# Bee_Hive_MainBoard.net
KiCad netlist of a schematic drawn in Altium Designer
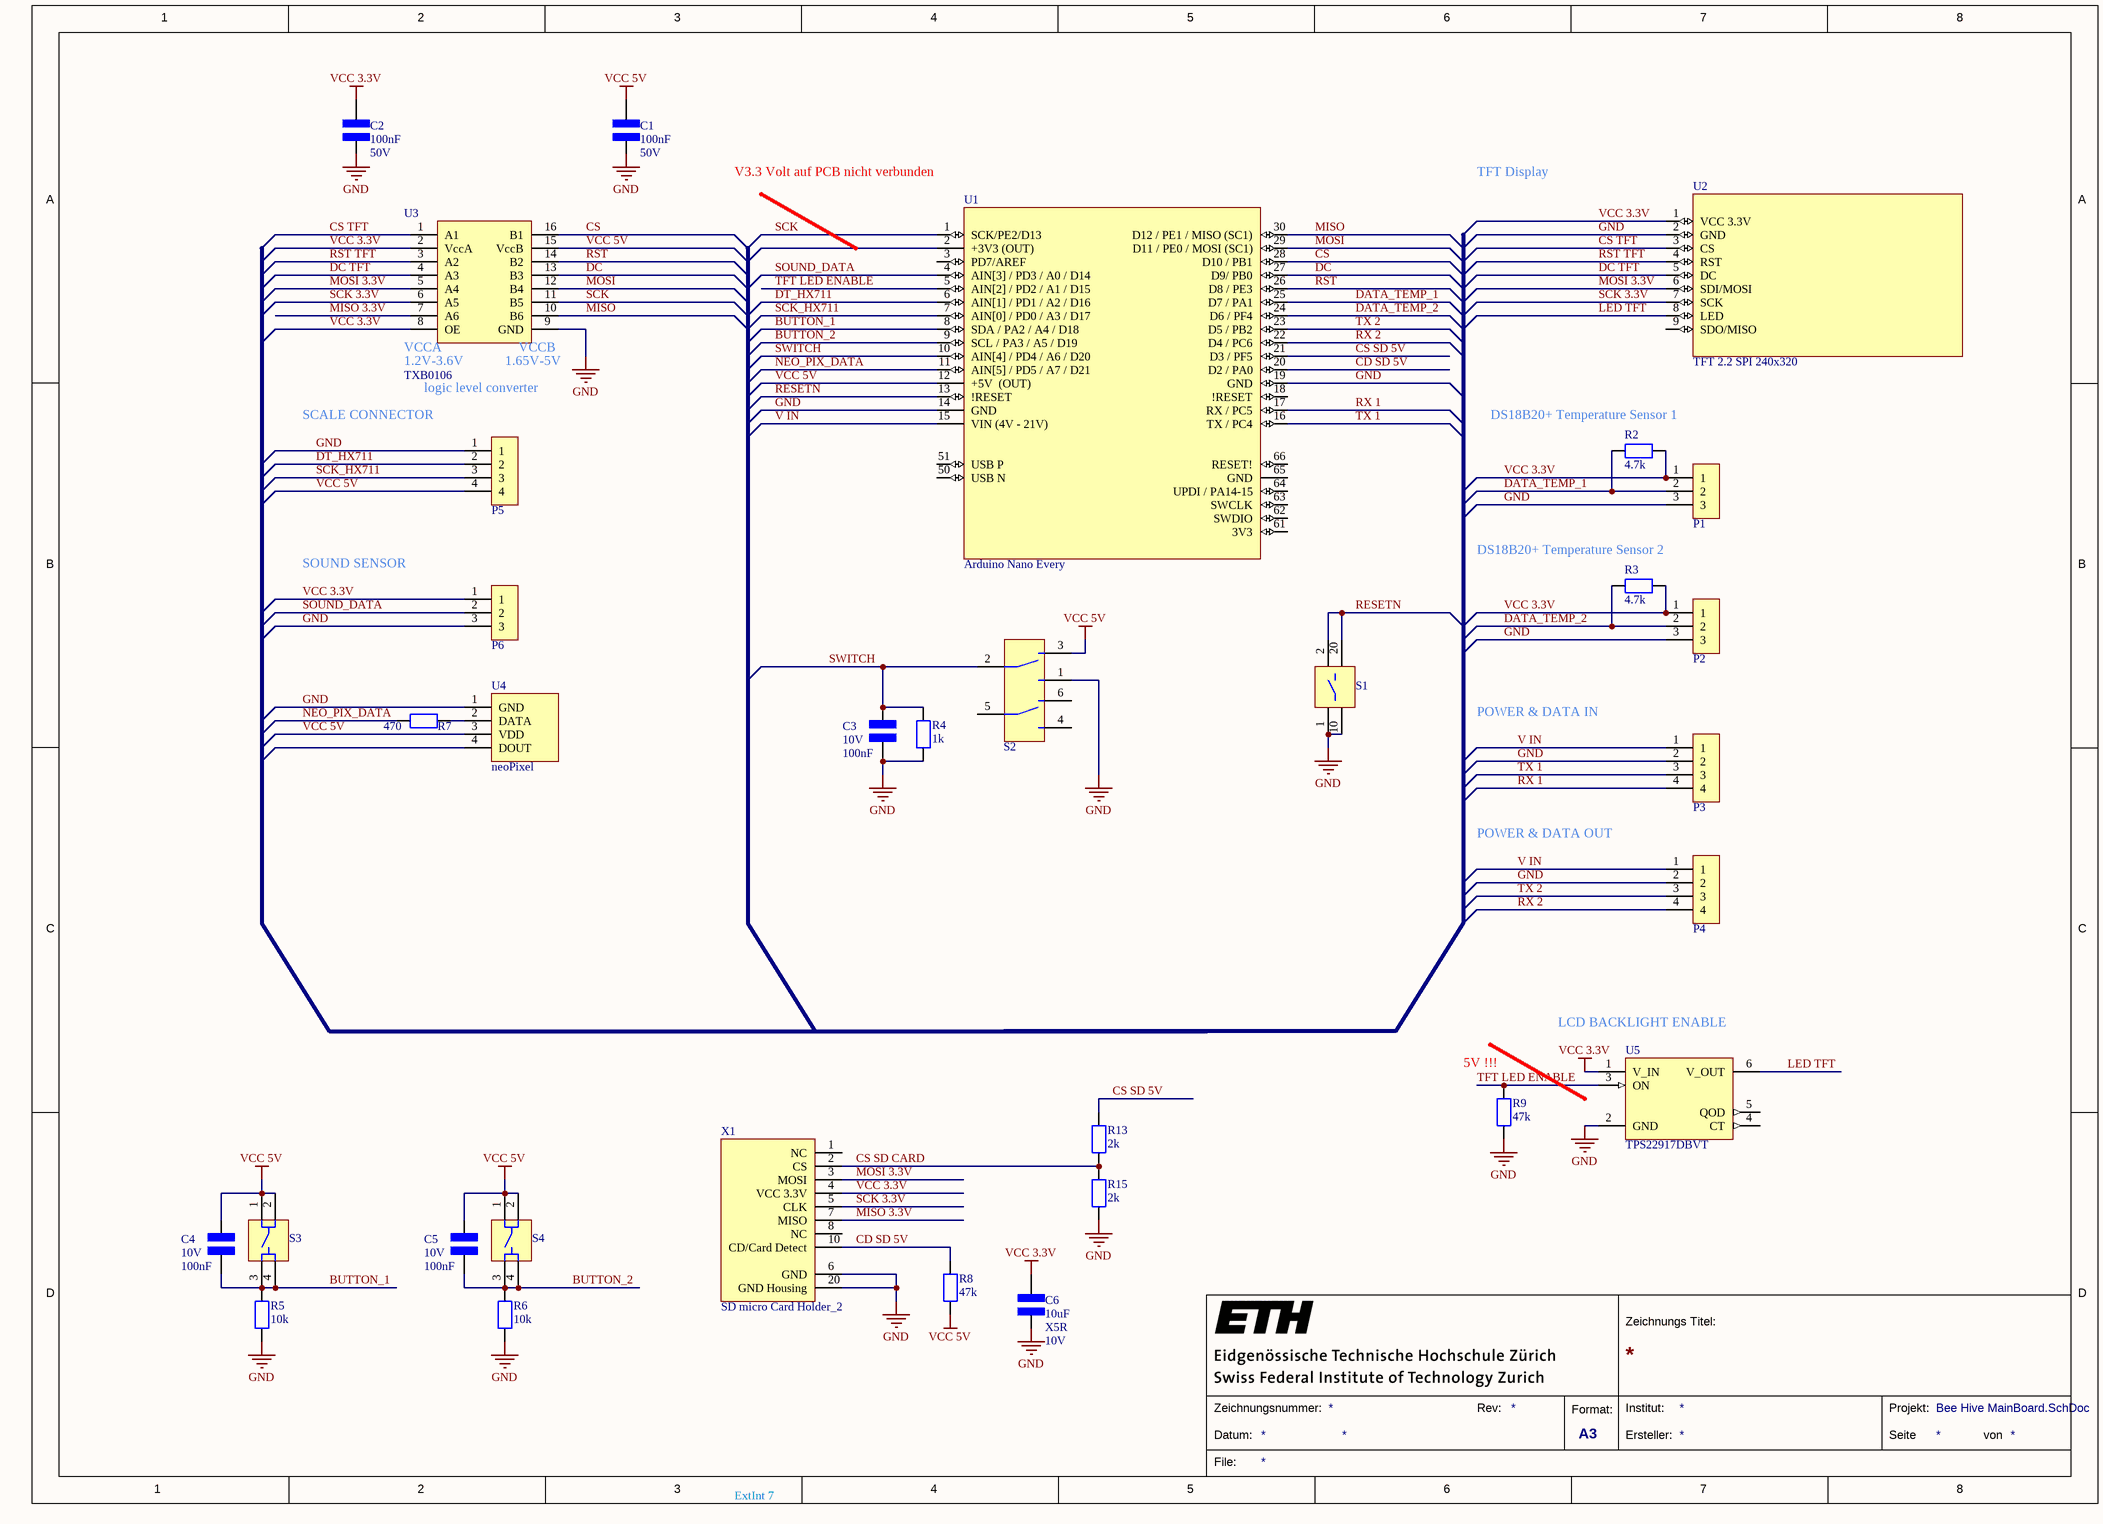
[diagram p0: Bee Hive MainBoard.SchDoc]

(export (version "E")
  (design (tool "Eeschema 10.0.6"))
  (components
    (comp (ref "C1")
      (value "100nF")
      (footprint "CAP 0603")
      (description "C CERAMIC SMD")
      (fields (field (name "UMAX") "50V") (field (name "Comment") "100nF 0603_1"))
      (libsource (lib "Library CAP") (part "100nF 0603_1"))
    )
    (comp (ref "C2")
      (value "100nF")
      (footprint "CAP 0603")
      (description "C CERAMIC SMD")
      (fields (field (name "UMAX") "50V") (field (name "Comment") "100nF 0603_1"))
      (libsource (lib "Library CAP") (part "100nF 0603_1"))
    )
    (comp (ref "C3")
      (value "100nF")
      (footprint "CAP 0603")
      (description "C CERAMIC SMD")
      (fields (field (name "UMAX") "10V") (field (name "Comment") "100nF 0603"))
      (libsource (lib "Library CAP") (part "100nF 0603"))
    )
    (comp (ref "C4")
      (value "100nF")
      (footprint "CAP 0603")
      (description "C CERAMIC SMD")
      (fields (field (name "UMAX") "10V") (field (name "Comment") "100nF 0603"))
      (libsource (lib "Library CAP") (part "100nF 0603"))
    )
    (comp (ref "C5")
      (value "100nF")
      (footprint "CAP 0603")
      (description "C CERAMIC SMD")
      (fields (field (name "UMAX") "10V") (field (name "Comment") "100nF 0603"))
      (libsource (lib "Library CAP") (part "100nF 0603"))
    )
    (comp (ref "C6")
      (value "10uF")
      (footprint "CAP 0603")
      (description "C CERAMIC SMD")
      (fields
        (field (name "DIELEKTRIKUM") "X5R")
        (field (name "UMAX") "10V")
        (field (name "Comment") "10uF 0603")
      )
      (libsource (lib "Library CAP") (part "10uF 0603"))
    )
    (comp (ref "P1")
      (value "3-Pin Right Angle Housing")
      (footprint "3PIN - RND 205-EK254-2.54-03P")
      (description "3-Pin")
      (libsource (lib "Library Scematic") (part "3-Pin Screw Terminal"))
    )
    (comp (ref "P2")
      (value "3-Pin Right Angle Housing")
      (footprint "3PIN - RND 205-EK254-2.54-03P")
      (description "3-Pin")
      (libsource (lib "Library Scematic") (part "3-Pin Screw Terminal"))
    )
    (comp (ref "P3")
      (value "4-Pin Right Angle Housing")
      (footprint "4PIN - RND 205-EK254-2.54-04P")
      (description "4-Pin")
      (libsource (lib "Library Scematic") (part "4-Pin Screw Terminal"))
    )
    (comp (ref "P4")
      (value "4-Pin Right Angle Housing")
      (footprint "4PIN - RND 205-EK254-2.54-04P")
      (description "4-Pin")
      (libsource (lib "Library Scematic") (part "4-Pin Screw Terminal"))
    )
    (comp (ref "P5")
      (value "4-Pin Right Angle Housing")
      (footprint "4PIN - RND 205-EK254-2.54-04P")
      (description "4-Pin")
      (libsource (lib "Library Scematic") (part "4-Pin Screw Terminal"))
    )
    (comp (ref "P6")
      (value "3-Pin Right Angle Housing")
      (footprint "3PIN - RND 205-EK254-2.54-03P")
      (description "3-Pin")
      (libsource (lib "Library Scematic") (part "3-Pin Screw Terminal"))
    )
    (comp (ref "R2")
      (value "4.7k")
      (footprint "RES 0603 FOOTPRINT")
      (description "R SMD")
      (fields (field (name "Comment") "4.7k Ohm 0603"))
      (libsource (lib "Library RES") (part "4.7k Ohm 0603"))
    )
    (comp (ref "R3")
      (value "4.7k")
      (footprint "RES 0603 FOOTPRINT")
      (description "R SMD")
      (fields (field (name "Comment") "4.7k Ohm 0603"))
      (libsource (lib "Library RES") (part "4.7k Ohm 0603"))
    )
    (comp (ref "R4")
      (value "1k")
      (footprint "RES 0603 FOOTPRINT")
      (description "R SMD")
      (fields (field (name "Comment") "1k Ohm 0603"))
      (libsource (lib "Library RES") (part "1k Ohm 0603"))
    )
    (comp (ref "R5")
      (value "10k")
      (footprint "RES 0603 FOOTPRINT")
      (description "R SMD")
      (fields (field (name "Comment") "10k Ohm 0603"))
      (libsource (lib "Library RES") (part "10k Ohm 0603"))
    )
    (comp (ref "R6")
      (value "10k")
      (footprint "RES 0603 FOOTPRINT")
      (description "R SMD")
      (fields (field (name "Comment") "10k Ohm 0603"))
      (libsource (lib "Library RES") (part "10k Ohm 0603"))
    )
    (comp (ref "R7")
      (value "470")
      (footprint "RES 0603 FOOTPRINT")
      (description "R SMD")
      (fields (field (name "Comment") "470 Ohm 0603"))
      (libsource (lib "Library RES") (part "470 Ohm 0603"))
    )
    (comp (ref "R8")
      (value "47k")
      (footprint "RES 0603 FOOTPRINT")
      (description "R SMD")
      (fields (field (name "Comment") "47k Ohm 0603"))
      (libsource (lib "Library RES") (part "47k Ohm 0603"))
    )
    (comp (ref "R9")
      (value "47k")
      (footprint "RES 0402 FOOTPRINT")
      (description "R SMD")
      (fields (field (name "Comment") "47k Ohm 0402"))
      (libsource (lib "Library RES") (part "47k Ohm 0402"))
    )
    (comp (ref "R13")
      (value "2k")
      (footprint "RES 0603 FOOTPRINT")
      (description "R SMD")
      (fields (field (name "Comment") "2k Ohm 0603"))
      (libsource (lib "Library RES") (part "2k Ohm 0603"))
    )
    (comp (ref "R15")
      (value "2k")
      (footprint "RES 0603 FOOTPRINT")
      (description "R SMD")
      (fields (field (name "Comment") "2k Ohm 0603"))
      (libsource (lib "Library RES") (part "2k Ohm 0603"))
    )
    (comp (ref "S1")
      (value "Taster Print_SMD_2")
      (footprint "Taster Print - SMD - KMR241G LFS")
      (description "Taster")
      (libsource (lib "Library Scematic") (part "Taster Print_SMD_2"))
    )
    (comp (ref "S2")
      (value "Schiebeschalter EG2207")
      (footprint "Schiebeschalter on-on 2 P, EG2207")
      (description "Schiebeschalter on-on PCM12SMTR")
      (libsource (lib "Library Scematic") (part "Schiebeschalter EG2207"))
    )
    (comp (ref "S3")
      (value "Taster Print_SMD_3")
      (footprint "Taster Print - SMD - PTS647SM70SMTR2LFS")
      (description "Taster")
      (libsource (lib "Library Scematic") (part "Taster Print_SMD_6"))
    )
    (comp (ref "S4")
      (value "Taster Print_SMD_3")
      (footprint "Taster Print - SMD - PTS647SM70SMTR2LFS")
      (description "Taster")
      (libsource (lib "Library Scematic") (part "Taster Print_SMD_6"))
    )
    (comp (ref "U1")
      (value "Arduino Nano Every")
      (footprint "Arduino Nano Every")
      (description "https://store.arduino.cc/nano-every-pack")
      (libsource (lib "Library Scematic") (part "Arduino Nano Every"))
    )
    (comp (ref "U2")
      (value "TFT 2.2 SPI 240x320")
      (footprint "TFT 2.2 SPI 240x320")
      (libsource (lib "Library Scematic") (part "TFT 2.2 SPI 240x320"))
    )
    (comp (ref "U3")
      (value "TXB0106")
      (footprint "TSSOP-16L")
      (description "Level Converter TXB0106")
      (libsource (lib "Library Scematic") (part "TXB0106 Level Converter"))
    )
    (comp (ref "U4")
      (value "neoPixel")
      (footprint "neoPixel 5050 adafruit 1655")
      (description "neoPixel 5050 adafruit 1655")
      (libsource (lib "Library Scematic") (part "neoPixel 5050 adafruit 1655"))
    )
    (comp (ref "U5")
      (value "TPS22917DBVT")
      (footprint "SOT23 - 6")
      (description "High Side Switch")
      (libsource (lib "Library Scematic") (part "TPS22917DBVT"))
    )
    (comp (ref "X1")
      (value "SD micro Card Holder_2")
      (footprint "SD Card Holder - micro - 2 - sd Card inserted")
      (description "SD micro Card  Holder")
      (libsource (lib "Library Scematic") (part "SD micro Card Holder_2"))
    )
  )
  (nets
    (net (code "1") (name "/BUTTON_1") (class "Default")
      (node (ref "C4") (pin "2") (pinfunction "2_2") (pintype "passive"))
      (node (ref "R5") (pin "2") (pinfunction "2_2") (pintype "passive"))
      (node (ref "S3") (pin "3") (pinfunction "3_3") (pintype "passive"))
      (node (ref "S3") (pin "4") (pinfunction "4_4") (pintype "passive"))
      (node (ref "U1") (pin "8") (pinfunction "SDA_/_PA2_/_A4_/_D18_8") (pintype "bidirectional"))
    )
    (net (code "2") (name "/BUTTON_2") (class "Default")
      (node (ref "C5") (pin "2") (pinfunction "2_2") (pintype "passive"))
      (node (ref "R6") (pin "2") (pinfunction "2_2") (pintype "passive"))
      (node (ref "S4") (pin "3") (pinfunction "3_3") (pintype "passive"))
      (node (ref "S4") (pin "4") (pinfunction "4_4") (pintype "passive"))
      (node (ref "U1") (pin "9") (pinfunction "SCL_/_PA3_/_A5_/_D19_9") (pintype "bidirectional"))
    )
    (net (code "3") (name "/CD SD 5V") (class "Default")
      (node (ref "R8") (pin "1") (pinfunction "1_1") (pintype "passive"))
      (node (ref "U1") (pin "20") (pinfunction "D2_/_PA0_20") (pintype "bidirectional"))
      (node (ref "X1") (pin "10") (pinfunction "CD/Card_Detect_10") (pintype "passive"))
    )
    (net (code "4") (name "/CS") (class "Default")
      (node (ref "U1") (pin "28") (pinfunction "D10_/_PB1_28") (pintype "bidirectional"))
      (node (ref "U3") (pin "16") (pinfunction "B1_16") (pintype "passive"))
    )
    (net (code "5") (name "/CS SD 5V") (class "Default")
      (node (ref "R13") (pin "2") (pinfunction "2_2") (pintype "passive"))
      (node (ref "U1") (pin "21") (pinfunction "D3_/_PF5_21") (pintype "bidirectional"))
    )
    (net (code "6") (name "/CS SD CARD") (class "Default")
      (node (ref "R13") (pin "1") (pinfunction "1_1") (pintype "passive"))
      (node (ref "R15") (pin "2") (pinfunction "2_2") (pintype "passive"))
      (node (ref "X1") (pin "2") (pinfunction "CS_2") (pintype "passive"))
    )
    (net (code "7") (name "/CS TFT") (class "Default")
      (node (ref "U2") (pin "3") (pinfunction "CS_3") (pintype "bidirectional"))
      (node (ref "U3") (pin "1") (pinfunction "A1_1") (pintype "power_in"))
    )
    (net (code "8") (name "/DATA_TEMP_1") (class "Default")
      (node (ref "P1") (pin "2") (pinfunction "2_2") (pintype "passive"))
      (node (ref "R2") (pin "2") (pinfunction "2_2") (pintype "passive"))
      (node (ref "U1") (pin "25") (pinfunction "D7_/_PA1_25") (pintype "bidirectional"))
    )
    (net (code "9") (name "/DATA_TEMP_2") (class "Default")
      (node (ref "P2") (pin "2") (pinfunction "2_2") (pintype "passive"))
      (node (ref "R3") (pin "2") (pinfunction "2_2") (pintype "passive"))
      (node (ref "U1") (pin "24") (pinfunction "D6_/_PF4_24") (pintype "bidirectional"))
    )
    (net (code "10") (name "/DC") (class "Default")
      (node (ref "U1") (pin "27") (pinfunction "D9/_PB0_27") (pintype "bidirectional"))
      (node (ref "U3") (pin "13") (pinfunction "B3_13") (pintype "passive"))
    )
    (net (code "11") (name "/DC TFT") (class "Default")
      (node (ref "U2") (pin "5") (pinfunction "DC_5") (pintype "bidirectional"))
      (node (ref "U3") (pin "4") (pinfunction "A3_4") (pintype "passive"))
    )
    (net (code "12") (name "/DT_HX711") (class "Default")
      (node (ref "P5") (pin "2") (pinfunction "2_2") (pintype "passive"))
      (node (ref "U1") (pin "6") (pinfunction "AIN[1]_/_PD1_/_A2_/_D16_6") (pintype "bidirectional"))
    )
    (net (code "13") (name "/LED TFT") (class "Default")
      (node (ref "U2") (pin "8") (pinfunction "LED_8") (pintype "bidirectional"))
      (node (ref "U5") (pin "6") (pinfunction "V_OUT_6") (pintype "power_in"))
    )
    (net (code "14") (name "/MISO") (class "Default")
      (node (ref "U1") (pin "30") (pinfunction "D12_/_PE1_/_MISO_(SC1)_30") (pintype "bidirectional"))
      (node (ref "U3") (pin "10") (pinfunction "B6_10") (pintype "passive"))
    )
    (net (code "15") (name "/MISO 3.3V") (class "Default")
      (node (ref "U3") (pin "7") (pinfunction "A6_7") (pintype "passive"))
      (node (ref "X1") (pin "7") (pinfunction "MISO_7") (pintype "passive"))
    )
    (net (code "16") (name "/MOSI") (class "Default")
      (node (ref "U1") (pin "29") (pinfunction "D11_/_PE0_/_MOSI_(SC1)_29") (pintype "bidirectional"))
      (node (ref "U3") (pin "12") (pinfunction "B4_12") (pintype "passive"))
    )
    (net (code "17") (name "/MOSI 3.3V") (class "Default")
      (node (ref "U2") (pin "6") (pinfunction "SDI/MOSI_6") (pintype "bidirectional"))
      (node (ref "U3") (pin "5") (pinfunction "A4_5") (pintype "passive"))
      (node (ref "X1") (pin "3") (pinfunction "MOSI_3") (pintype "passive"))
    )
    (net (code "18") (name "/NEO_PIX_DATA") (class "Default")
      (node (ref "R7") (pin "1") (pinfunction "1_1") (pintype "passive"))
      (node (ref "U1") (pin "11") (pinfunction "AIN[5]_/_PD5_/_A7_/_D21_11") (pintype "bidirectional"))
    )
    (net (code "19") (name "/RESETN") (class "Default")
      (node (ref "S1") (pin "2") (pinfunction "2_2") (pintype "passive"))
      (node (ref "S1") (pin "20") (pinfunction "20_20") (pintype "passive"))
      (node (ref "U1") (pin "13") (pinfunction "!RESET_13") (pintype "bidirectional"))
    )
    (net (code "20") (name "/RST") (class "Default")
      (node (ref "U1") (pin "26") (pinfunction "D8_/_PE3_26") (pintype "bidirectional"))
      (node (ref "U3") (pin "14") (pinfunction "B2_14") (pintype "passive"))
    )
    (net (code "21") (name "/RST TFT") (class "Default")
      (node (ref "U2") (pin "4") (pinfunction "RST_4") (pintype "bidirectional"))
      (node (ref "U3") (pin "3") (pinfunction "A2_3") (pintype "passive"))
    )
    (net (code "22") (name "/RX 1") (class "Default")
      (node (ref "P3") (pin "4") (pinfunction "4_4") (pintype "passive"))
      (node (ref "U1") (pin "17") (pinfunction "RX_/_PC5_17") (pintype "bidirectional"))
    )
    (net (code "23") (name "/RX 2") (class "Default")
      (node (ref "P4") (pin "4") (pinfunction "4_4") (pintype "passive"))
      (node (ref "U1") (pin "22") (pinfunction "D4_/_PC6_22") (pintype "bidirectional"))
    )
    (net (code "24") (name "/SCK") (class "Default")
      (node (ref "U1") (pin "1") (pinfunction "SCK/PE2/D13_1") (pintype "bidirectional"))
      (node (ref "U3") (pin "11") (pinfunction "B5_11") (pintype "passive"))
    )
    (net (code "25") (name "/SCK 3.3V") (class "Default")
      (node (ref "U2") (pin "7") (pinfunction "SCK_7") (pintype "bidirectional"))
      (node (ref "U3") (pin "6") (pinfunction "A5_6") (pintype "passive"))
      (node (ref "X1") (pin "5") (pinfunction "CLK_5") (pintype "passive"))
    )
    (net (code "26") (name "/SCK_HX711") (class "Default")
      (node (ref "P5") (pin "3") (pinfunction "3_3") (pintype "passive"))
      (node (ref "U1") (pin "7") (pinfunction "AIN[0]_/_PD0_/_A3_/_D17_7") (pintype "bidirectional"))
    )
    (net (code "27") (name "/SOUND_DATA") (class "Default")
      (node (ref "P6") (pin "2") (pinfunction "2_2") (pintype "passive"))
      (node (ref "U1") (pin "4") (pinfunction "AIN[3]_/_PD3_/_A0_/_D14_4") (pintype "bidirectional"))
    )
    (net (code "28") (name "/SWITCH") (class "Default")
      (node (ref "C3") (pin "1") (pinfunction "1_1") (pintype "passive"))
      (node (ref "R4") (pin "2") (pinfunction "2_2") (pintype "passive"))
      (node (ref "S2") (pin "2") (pinfunction "2_2") (pintype "passive"))
      (node (ref "U1") (pin "10") (pinfunction "AIN[4]_/_PD4_/_A6_/_D20_10") (pintype "bidirectional"))
    )
    (net (code "29") (name "/TFT LED ENABLE") (class "Default")
      (node (ref "R9") (pin "2") (pinfunction "2_2") (pintype "passive"))
      (node (ref "U1") (pin "5") (pinfunction "AIN[2]_/_PD2_/_A1_/_D15_5") (pintype "bidirectional"))
      (node (ref "U5") (pin "3") (pinfunction "ON_3") (pintype "input"))
    )
    (net (code "30") (name "/TX 1") (class "Default")
      (node (ref "P3") (pin "3") (pinfunction "3_3") (pintype "passive"))
      (node (ref "U1") (pin "16") (pinfunction "TX_/_PC4_16") (pintype "bidirectional"))
    )
    (net (code "31") (name "/TX 2") (class "Default")
      (node (ref "P4") (pin "3") (pinfunction "3_3") (pintype "passive"))
      (node (ref "U1") (pin "23") (pinfunction "D5_/_PB2_23") (pintype "bidirectional"))
    )
    (net (code "32") (name "/V IN") (class "Default")
      (node (ref "P3") (pin "1") (pinfunction "1_1") (pintype "passive"))
      (node (ref "P4") (pin "1") (pinfunction "1_1") (pintype "passive"))
      (node (ref "U1") (pin "15") (pinfunction "VIN_(4V_-_21V)_15") (pintype "power_in"))
    )
    (net (code "33") (name "GND") (class "Default")
      (node (ref "C1") (pin "1") (pinfunction "1_1") (pintype "passive"))
      (node (ref "C2") (pin "1") (pinfunction "1_1") (pintype "passive"))
      (node (ref "C3") (pin "2") (pinfunction "2_2") (pintype "passive"))
      (node (ref "C6") (pin "1") (pinfunction "1_1") (pintype "passive"))
      (node (ref "P1") (pin "3") (pinfunction "3_3") (pintype "passive"))
      (node (ref "P2") (pin "3") (pinfunction "3_3") (pintype "passive"))
      (node (ref "P3") (pin "2") (pinfunction "2_2") (pintype "passive"))
      (node (ref "P4") (pin "2") (pinfunction "2_2") (pintype "passive"))
      (node (ref "P5") (pin "1") (pinfunction "1_1") (pintype "passive"))
      (node (ref "P6") (pin "3") (pinfunction "3_3") (pintype "passive"))
      (node (ref "R15") (pin "1") (pinfunction "1_1") (pintype "passive"))
      (node (ref "R4") (pin "1") (pinfunction "1_1") (pintype "passive"))
      (node (ref "R5") (pin "1") (pinfunction "1_1") (pintype "passive"))
      (node (ref "R6") (pin "1") (pinfunction "1_1") (pintype "passive"))
      (node (ref "R9") (pin "1") (pinfunction "1_1") (pintype "passive"))
      (node (ref "S1") (pin "1") (pinfunction "1_1") (pintype "passive"))
      (node (ref "S1") (pin "10") (pinfunction "10_10") (pintype "passive"))
      (node (ref "S2") (pin "1") (pinfunction "1_1") (pintype "passive"))
      (node (ref "U1") (pin "14") (pinfunction "GND_14") (pintype "power_in"))
      (node (ref "U1") (pin "19") (pinfunction "GND_19") (pintype "bidirectional"))
      (node (ref "U2") (pin "2") (pinfunction "GND_2") (pintype "bidirectional"))
      (node (ref "U3") (pin "9") (pinfunction "GND_9") (pintype "passive"))
      (node (ref "U4") (pin "1") (pinfunction "GND_1") (pintype "passive"))
      (node (ref "U5") (pin "2") (pinfunction "GND_2") (pintype "power_in"))
      (node (ref "X1") (pin "20") (pinfunction "GND_Housing_20") (pintype "passive"))
      (node (ref "X1") (pin "6") (pinfunction "GND_6") (pintype "passive"))
    )
    (net (code "34") (name "Net-(U4-DATA)") (class "Default")
      (node (ref "R7") (pin "2") (pinfunction "2_2") (pintype "passive"))
      (node (ref "U4") (pin "2") (pinfunction "DATA_2") (pintype "passive"))
    )
    (net (code "35") (name "VCC 3.3V") (class "Default")
      (node (ref "C2") (pin "2") (pinfunction "2_2") (pintype "passive"))
      (node (ref "C6") (pin "2") (pinfunction "2_2") (pintype "passive"))
      (node (ref "P1") (pin "1") (pinfunction "1_1") (pintype "passive"))
      (node (ref "P2") (pin "1") (pinfunction "1_1") (pintype "passive"))
      (node (ref "P6") (pin "1") (pinfunction "1_1") (pintype "passive"))
      (node (ref "R2") (pin "1") (pinfunction "1_1") (pintype "passive"))
      (node (ref "R3") (pin "1") (pinfunction "1_1") (pintype "passive"))
      (node (ref "U2") (pin "1") (pinfunction "VCC_3.3V_1") (pintype "bidirectional"))
      (node (ref "U3") (pin "2") (pinfunction "VccA_2") (pintype "passive"))
      (node (ref "U3") (pin "8") (pinfunction "OE_8") (pintype "passive"))
      (node (ref "U5") (pin "1") (pinfunction "V_IN_1") (pintype "power_in"))
      (node (ref "X1") (pin "4") (pinfunction "VCC_3.3V_4") (pintype "passive"))
    )
    (net (code "36") (name "VCC 5V") (class "Default")
      (node (ref "C1") (pin "2") (pinfunction "2_2") (pintype "passive"))
      (node (ref "C4") (pin "1") (pinfunction "1_1") (pintype "passive"))
      (node (ref "C5") (pin "1") (pinfunction "1_1") (pintype "passive"))
      (node (ref "P5") (pin "4") (pinfunction "4_4") (pintype "passive"))
      (node (ref "R8") (pin "2") (pinfunction "2_2") (pintype "passive"))
      (node (ref "S2") (pin "3") (pinfunction "3_3") (pintype "passive"))
      (node (ref "S3") (pin "1") (pinfunction "1_1") (pintype "passive"))
      (node (ref "S3") (pin "2") (pinfunction "2_2") (pintype "passive"))
      (node (ref "S4") (pin "1") (pinfunction "1_1") (pintype "passive"))
      (node (ref "S4") (pin "2") (pinfunction "2_2") (pintype "passive"))
      (node (ref "U1") (pin "12") (pinfunction "+5V__(OUT)_12") (pintype "power_in"))
      (node (ref "U3") (pin "15") (pinfunction "VccB_15") (pintype "passive"))
      (node (ref "U4") (pin "3") (pinfunction "VDD_3") (pintype "passive"))
    )
    (net (code "37") (name "unconnected-(S2-Pad4)") (class "Default")
      (node (ref "S2") (pin "4") (pinfunction "4_4") (pintype "passive"))
    )
    (net (code "38") (name "unconnected-(S2-Pad5)") (class "Default")
      (node (ref "S2") (pin "5") (pinfunction "5_5") (pintype "passive"))
    )
    (net (code "39") (name "unconnected-(S2-Pad6)") (class "Default")
      (node (ref "S2") (pin "6") (pinfunction "6_6") (pintype "passive"))
    )
    (net (code "40") (name "unconnected-(U1-!RESET-Pad18)") (class "Default")
      (node (ref "U1") (pin "18") (pinfunction "!RESET_18") (pintype "bidirectional"))
    )
    (net (code "41") (name "unconnected-(U1-+3V3_(OUT)-Pad2)") (class "Default")
      (node (ref "U1") (pin "2") (pinfunction "+3V3_(OUT)_2") (pintype "power_in"))
    )
    (net (code "42") (name "unconnected-(U1-3V3-Pad61)") (class "Default")
      (node (ref "U1") (pin "61") (pinfunction "3V3_61") (pintype "bidirectional"))
    )
    (net (code "43") (name "unconnected-(U1-GND-Pad65)") (class "Default")
      (node (ref "U1") (pin "65") (pinfunction "GND_65") (pintype "power_in"))
    )
    (net (code "44") (name "unconnected-(U1-PD7{slash}AREF-Pad3)") (class "Default")
      (node (ref "U1") (pin "3") (pinfunction "PD7/AREF_3") (pintype "bidirectional"))
    )
    (net (code "45") (name "unconnected-(U1-RESET!-Pad66)") (class "Default")
      (node (ref "U1") (pin "66") (pinfunction "RESET!_66") (pintype "bidirectional"))
    )
    (net (code "46") (name "unconnected-(U1-SWCLK-Pad63)") (class "Default")
      (node (ref "U1") (pin "63") (pinfunction "SWCLK_63") (pintype "bidirectional"))
    )
    (net (code "47") (name "unconnected-(U1-SWDIO-Pad62)") (class "Default")
      (node (ref "U1") (pin "62") (pinfunction "SWDIO_62") (pintype "bidirectional"))
    )
    (net (code "48") (name "unconnected-(U1-UPDI_{slash}_PA14-15-Pad64)") (class "Default")
      (node (ref "U1") (pin "64") (pinfunction "UPDI_/_PA14-15_64") (pintype "bidirectional"))
    )
    (net (code "49") (name "unconnected-(U1-USB_N-Pad50)") (class "Default")
      (node (ref "U1") (pin "50") (pinfunction "USB_N_50") (pintype "bidirectional"))
    )
    (net (code "50") (name "unconnected-(U1-USB_P-Pad51)") (class "Default")
      (node (ref "U1") (pin "51") (pinfunction "USB_P_51") (pintype "bidirectional"))
    )
    (net (code "51") (name "unconnected-(U2-SDO{slash}MISO-Pad9)") (class "Default")
      (node (ref "U2") (pin "9") (pinfunction "SDO/MISO_9") (pintype "bidirectional"))
    )
    (net (code "52") (name "unconnected-(U4-DOUT-Pad4)") (class "Default")
      (node (ref "U4") (pin "4") (pinfunction "DOUT_4") (pintype "passive"))
    )
    (net (code "53") (name "unconnected-(U5-CT-Pad4)") (class "Default")
      (node (ref "U5") (pin "4") (pinfunction "CT_4") (pintype "output"))
    )
    (net (code "54") (name "unconnected-(U5-QOD-Pad5)") (class "Default")
      (node (ref "U5") (pin "5") (pinfunction "QOD_5") (pintype "output"))
    )
    (net (code "55") (name "unconnected-(X1-NC-Pad1)") (class "Default")
      (node (ref "X1") (pin "1") (pinfunction "NC_1") (pintype "passive"))
    )
    (net (code "56") (name "unconnected-(X1-NC-Pad8)") (class "Default")
      (node (ref "X1") (pin "8") (pinfunction "NC_8") (pintype "passive"))
    )
  )
)
